# DistanceSensor.net
KiCad netlist of a schematic drawn in Altium Designer
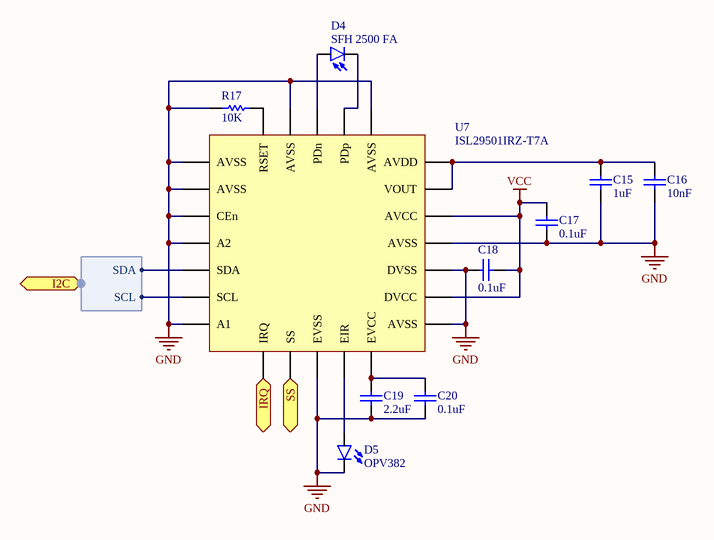
[diagram p0: DistanceSensor.SchDoc]

(export (version "E")
  (design (tool "Eeschema 10.0.6"))
  (components
    (comp (ref "C15")
      (value "1uF")
      (footprint "C0402[1005X55]")
      (description "1uF 6.3V 10% 0402 (1005 Metric)")
      (fields (field (name "PARTNUMBER") "GRM155R70J105KA12D") (field (name "MANUFACTURER") "Murata"))
      (libsource (lib "Capacitors") (part "CAP_1uF_6.3V_0402_10%"))
    )
    (comp (ref "C16")
      (value "10nF")
      (footprint "C0402[1005X55]")
      (description "10nF 50V 10% 0402 (1005 Metric)")
      (fields (field (name "PARTNUMBER") "GCM155R71H103KA55D") (field (name "MANUFACTURER") "Murata"))
      (libsource (lib "Capacitors") (part "CAP_10nF_50V_0402_10%"))
    )
    (comp (ref "C17")
      (value "0.1uF")
      (footprint "C0402[1005X55]")
      (description "0.1uF 6.3V 10% 0402 (1005 Metric)")
      (fields (field (name "PARTNUMBER") "GRM155R70J104KA01D") (field (name "MANUFACTURER") "Murata"))
      (libsource (lib "Capacitors") (part "CAP_0.1uF_6.3V_0402_10%"))
    )
    (comp (ref "C18")
      (value "0.1uF")
      (footprint "C0402[1005X55]")
      (description "0.1uF 6.3V 10% 0402 (1005 Metric)")
      (fields (field (name "PARTNUMBER") "GRM155R70J104KA01D") (field (name "MANUFACTURER") "Murata"))
      (libsource (lib "Capacitors") (part "CAP_0.1uF_6.3V_0402_10%"))
    )
    (comp (ref "C19")
      (value "2.2uF")
      (footprint "C0402[1005X55]")
      (description "2.2uF 6.3V 20% 0402 (1005 Metric)")
      (fields (field (name "PARTNUMBER") "GRM155R60J225ME15D") (field (name "MANUFACTURER") "Murata"))
      (libsource (lib "Capacitors") (part "CAP_2.2uF_6.3V_0402_20%"))
    )
    (comp (ref "C20")
      (value "0.1uF")
      (footprint "C0402[1005X55]")
      (description "0.1uF 6.3V 10% 0402 (1005 Metric)")
      (fields (field (name "PARTNUMBER") "GRM155R70J104KA01D") (field (name "MANUFACTURER") "Murata"))
      (libsource (lib "Capacitors") (part "CAP_0.1uF_6.3V_0402_10%"))
    )
    (comp (ref "D4")
      (value "SFH 2500 FA")
      (footprint "SFH 2500 FA")
      (fields (field (name "MANUFACTURER") "Osram"))
      (libsource (lib "Components") (part "SFH 2500 FA"))
    )
    (comp (ref "D5")
      (value "OPV382")
      (footprint "OPV382")
      (fields (field (name "MANUFACTURER") "OPTEK Technology"))
      (libsource (lib "Components") (part "OPV382"))
    )
    (comp (ref "R17")
      (value "10K")
      (footprint "R0402[1005]")
      (description "10K 0.063W 1% 0402 (1005 Metric)")
      (fields (field (name "MANUFACTURER") "KOA Speer") (field (name "PARTNUMBER") "RK73H1ETTP1002F"))
      (libsource (lib "Resistors") (part "RES_10K_0402_1%"))
    )
    (comp (ref "U7")
      (value "ISL29501IRZ-T7A")
      (footprint "QFN-24")
      (description "IC TOF SIGNAL PROCESSOR 24QFN")
      (fields (field (name "MANUFACTURER") "Intersil"))
      (libsource (lib "ICs") (part "ISL29501IRZ-T7A"))
    )
  )
  (nets
    (net (code "2") (name "/IRQ") (class "Default")
      (node (ref "U7") (pin "8") (pinfunction "IRQ_8") (pintype "passive"))
    )
    (net (code "3") (name "/SCL") (class "Default")
      (node (ref "U7") (pin "6") (pinfunction "SCL_6") (pintype "passive"))
    )
    (net (code "4") (name "/SDA") (class "Default")
      (node (ref "U7") (pin "5") (pinfunction "SDA_5") (pintype "passive"))
    )
    (net (code "5") (name "/SS") (class "Default")
      (node (ref "U7") (pin "9") (pinfunction "SS_9") (pintype "passive"))
    )
    (net (code "7") (name "GND") (class "Default")
      (node (ref "C15") (pin "1") (pinfunction "1_1") (pintype "passive"))
      (node (ref "C16") (pin "1") (pinfunction "1_1") (pintype "passive"))
      (node (ref "C17") (pin "2") (pinfunction "2_2") (pintype "passive"))
      (node (ref "C18") (pin "2") (pinfunction "2_2") (pintype "passive"))
      (node (ref "C19") (pin "1") (pinfunction "1_1") (pintype "passive"))
      (node (ref "C20") (pin "1") (pinfunction "1_1") (pintype "passive"))
      (node (ref "D5") (pin "1") (pinfunction "C_1") (pintype "passive"))
      (node (ref "R17") (pin "1") (pinfunction "1_1") (pintype "passive"))
      (node (ref "U7") (pin "1") (pinfunction "AVSS_1") (pintype "passive"))
      (node (ref "U7") (pin "10") (pinfunction "EVSS_10") (pintype "passive"))
      (node (ref "U7") (pin "13") (pinfunction "AVSS_13") (pintype "passive"))
      (node (ref "U7") (pin "15") (pinfunction "DVSS_15") (pintype "passive"))
      (node (ref "U7") (pin "16") (pinfunction "AVSS_16") (pintype "passive"))
      (node (ref "U7") (pin "2") (pinfunction "AVSS_2") (pintype "passive"))
      (node (ref "U7") (pin "20") (pinfunction "AVSS_20") (pintype "passive"))
      (node (ref "U7") (pin "23") (pinfunction "AVSS_23") (pintype "passive"))
      (node (ref "U7") (pin "3") (pinfunction "CEn_3") (pintype "passive"))
      (node (ref "U7") (pin "4") (pinfunction "A2_4") (pintype "power_in"))
      (node (ref "U7") (pin "7") (pinfunction "A1_7") (pintype "passive"))
    )
    (net (code "8") (name "Net-(D4-A)") (class "Default")
      (node (ref "D4") (pin "2") (pinfunction "A_2") (pintype "passive"))
      (node (ref "U7") (pin "22") (pinfunction "PDn_22") (pintype "passive"))
    )
    (net (code "9") (name "Net-(D4-C)") (class "Default")
      (node (ref "D4") (pin "1") (pinfunction "C_1") (pintype "passive"))
      (node (ref "U7") (pin "21") (pinfunction "PDp_21") (pintype "passive"))
    )
    (net (code "10") (name "Net-(D5-A)") (class "Default")
      (node (ref "D5") (pin "2") (pinfunction "A_2") (pintype "passive"))
      (node (ref "U7") (pin "11") (pinfunction "EIR_11") (pintype "passive"))
    )
    (net (code "11") (name "Net-(U7-AVDD)") (class "Default")
      (node (ref "C15") (pin "2") (pinfunction "2_2") (pintype "passive"))
      (node (ref "C16") (pin "2") (pinfunction "2_2") (pintype "passive"))
      (node (ref "U7") (pin "18") (pinfunction "VOUT_18") (pintype "passive"))
      (node (ref "U7") (pin "19") (pinfunction "AVDD_19") (pintype "passive"))
    )
    (net (code "12") (name "Net-(U7-EVCC)") (class "Default")
      (node (ref "C19") (pin "2") (pinfunction "2_2") (pintype "passive"))
      (node (ref "C20") (pin "2") (pinfunction "2_2") (pintype "passive"))
      (node (ref "U7") (pin "12") (pinfunction "EVCC_12") (pintype "passive"))
    )
    (net (code "13") (name "Net-(U7-RSET)") (class "Default")
      (node (ref "R17") (pin "2") (pinfunction "2_2") (pintype "passive"))
      (node (ref "U7") (pin "24") (pinfunction "RSET_24") (pintype "passive"))
    )
    (net (code "14") (name "VCC") (class "Default")
      (node (ref "C17") (pin "1") (pinfunction "1_1") (pintype "passive"))
      (node (ref "C18") (pin "1") (pinfunction "1_1") (pintype "passive"))
      (node (ref "U7") (pin "14") (pinfunction "DVCC_14") (pintype "passive"))
      (node (ref "U7") (pin "17") (pinfunction "AVCC_17") (pintype "passive"))
    )
  )
)
